# TPDH-Walrus_4pinPTH.net
KiCad netlist of a schematic drawn in EAGLE
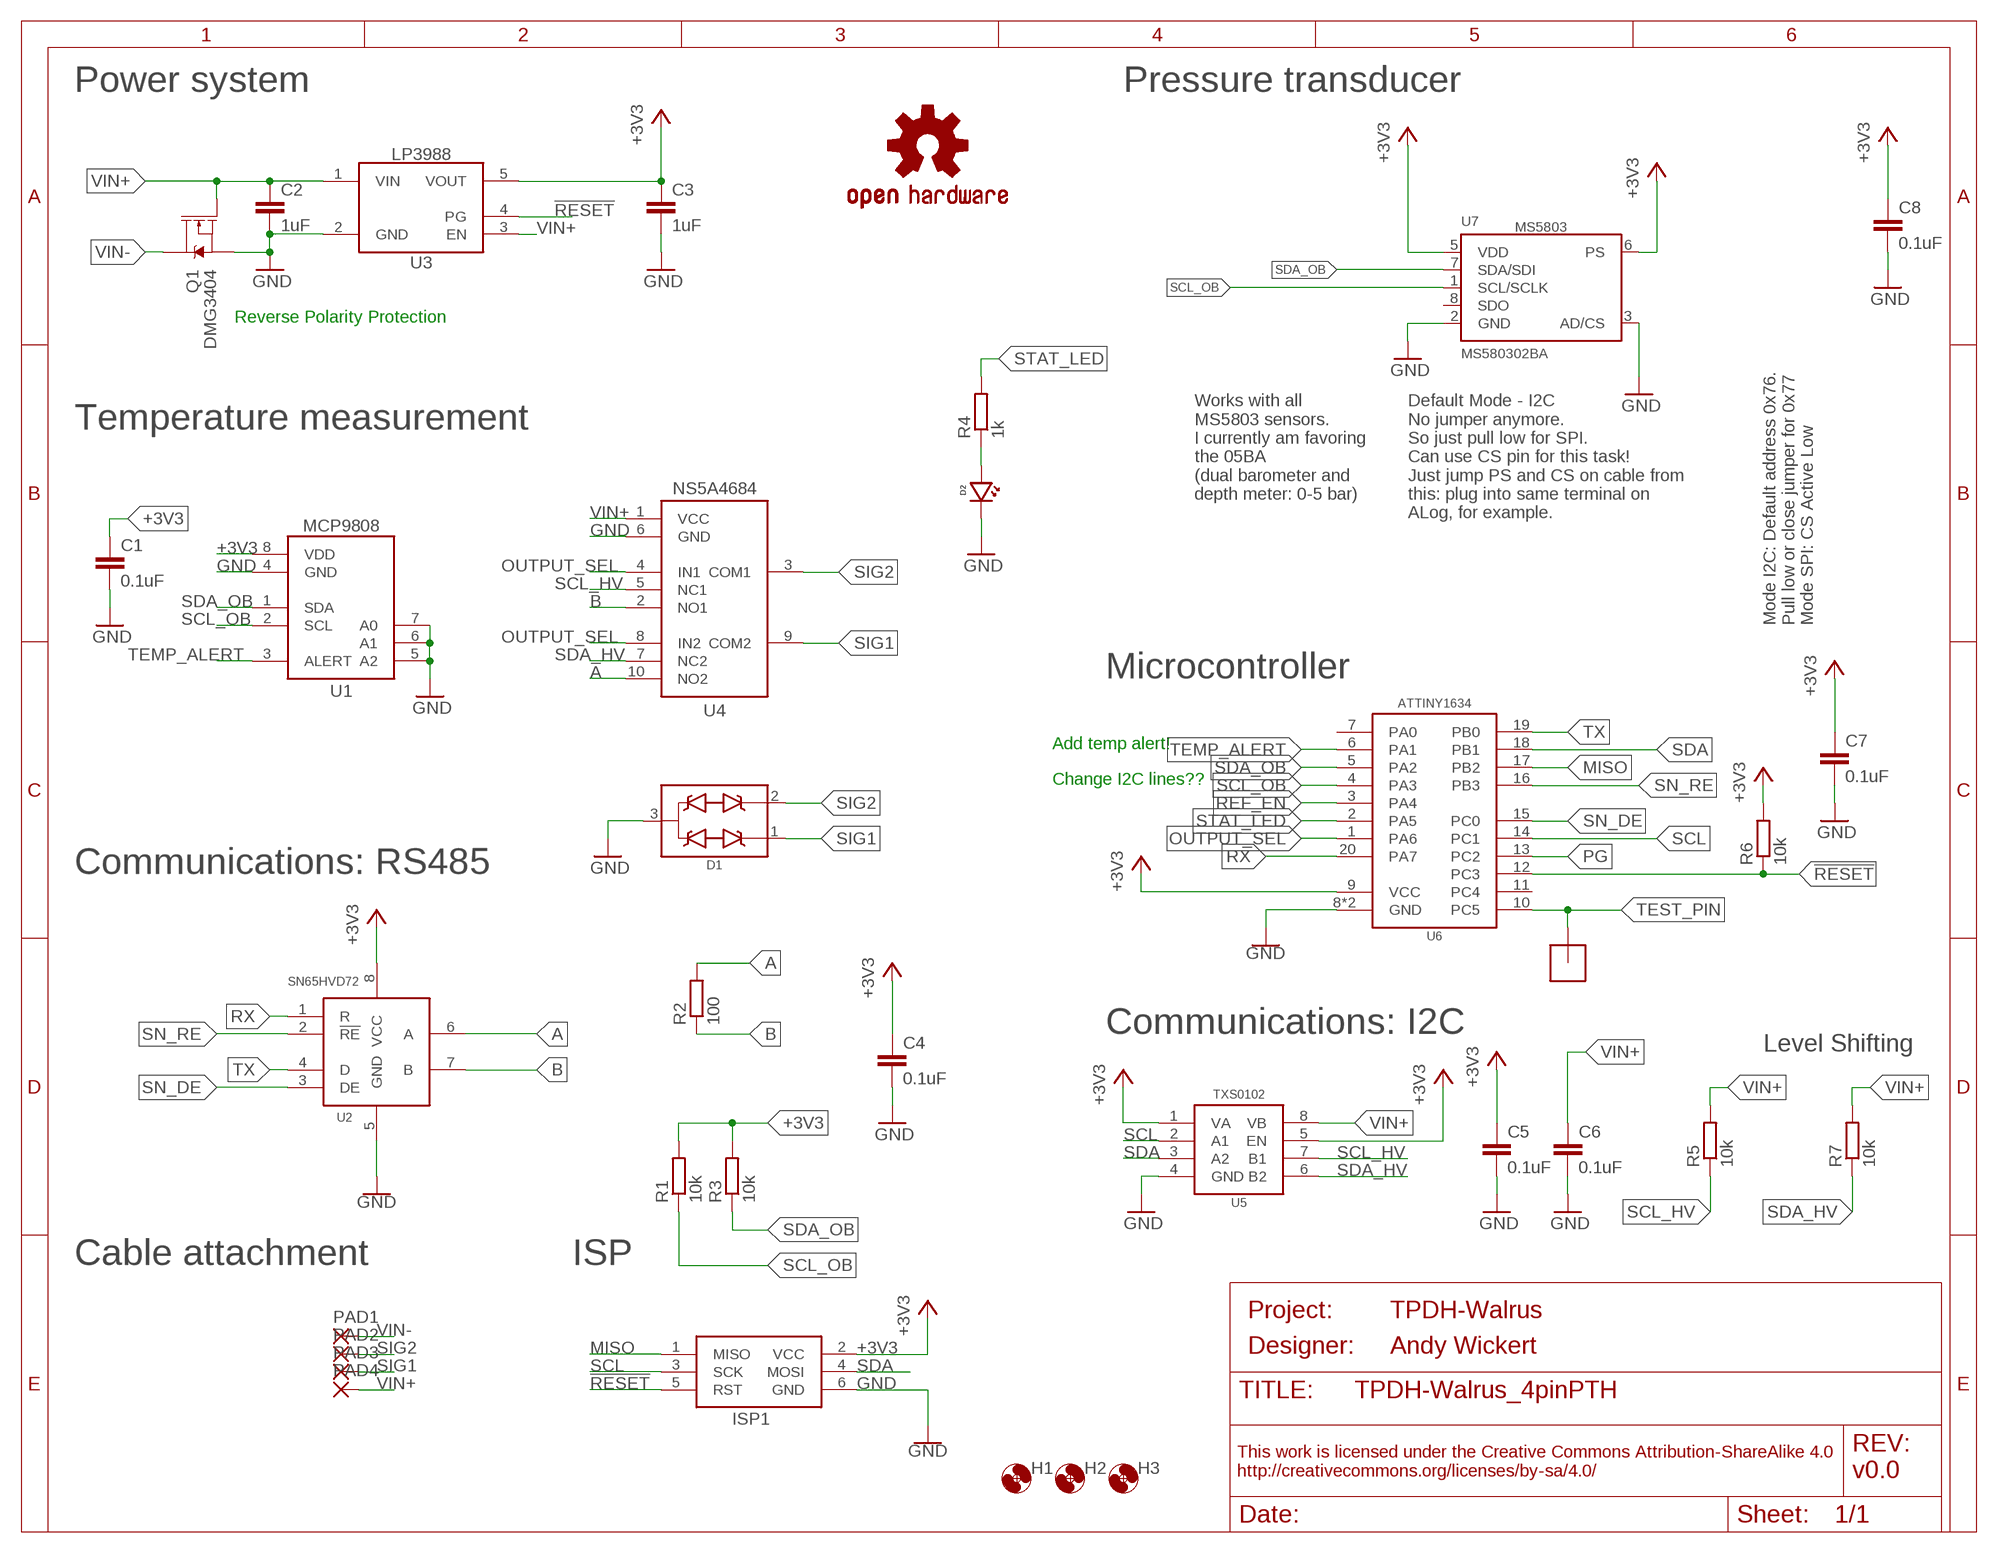
[diagram p0: schematic, sheet 1]

(export (version "E")
  (design (tool "Eeschema 10.0.6"))
  (components
    (comp (ref "C1")
      (value "0.1uF")
      (footprint "eagle-import:C0402")
      (fields (field (name "MF") "Murata") (field (name "MPN") "GCM155R71C104KA55D"))
      (libsource (lib "eagle-import") (part "C-EUC04020.1UF"))
    )
    (comp (ref "C2")
      (value "1uF")
      (footprint "eagle-import:C0603")
      (fields (field (name "MF") "Samsung") (field (name "MPN") "1276-6524-1-ND"))
      (libsource (lib "eagle-import") (part "C-EUC06031UF"))
    )
    (comp (ref "C3")
      (value "1uF")
      (footprint "eagle-import:C0603")
      (fields (field (name "MF") "Samsung") (field (name "MPN") "1276-6524-1-ND"))
      (libsource (lib "eagle-import") (part "C-EUC06031UF"))
    )
    (comp (ref "C4")
      (value "0.1uF")
      (footprint "eagle-import:C0402")
      (fields (field (name "MF") "Murata") (field (name "MPN") "GCM155R71C104KA55D"))
      (libsource (lib "eagle-import") (part "C-EUC04020.1UF"))
    )
    (comp (ref "C5")
      (value "0.1uF")
      (footprint "eagle-import:C0402")
      (fields (field (name "MF") "Murata") (field (name "MPN") "GCM155R71C104KA55D"))
      (libsource (lib "eagle-import") (part "C-EUC04020.1UF"))
    )
    (comp (ref "C6")
      (value "0.1uF")
      (footprint "eagle-import:C0402")
      (fields (field (name "MF") "Murata") (field (name "MPN") "GCM155R71C104KA55D"))
      (libsource (lib "eagle-import") (part "C-EUC04020.1UF"))
    )
    (comp (ref "C7")
      (value "0.1uF")
      (footprint "eagle-import:C0402")
      (fields (field (name "MF") "Murata") (field (name "MPN") "GCM155R71C104KA55D"))
      (libsource (lib "eagle-import") (part "C-EUC04020.1UF"))
    )
    (comp (ref "C8")
      (value "0.1uF")
      (footprint "eagle-import:C0402")
      (fields (field (name "MF") "Murata") (field (name "MPN") "GCM155R71C104KA55D"))
      (libsource (lib "eagle-import") (part "C-EUC04020.1UF"))
    )
    (comp (ref "D1")
      (value "TVSSM712")
      (footprint "eagle-import:SOT23-3")
      (fields (field (name "MF") "Bourns") (field (name "MPN") "CDSOT23-SM712"))
      (libsource (lib "eagle-import") (part "TVSSM712"))
    )
    (comp (ref "D2")
      (value "LEDBLUE0603")
      (footprint "eagle-import:LED_0603")
      (fields (field (name "MF") "Wurth") (field (name "MPN") "150060BS75000"))
      (libsource (lib "eagle-import") (part "LED0603BLUE"))
    )
    (comp (ref "H1")
      (value "MOUNTING_HOLE2_NP")
      (footprint "eagle-import:2_56")
      (libsource (lib "eagle-import") (part "MOUNTING_HOLE2_NP"))
    )
    (comp (ref "H2")
      (value "MOUNTING_HOLE2_NP")
      (footprint "eagle-import:2_56")
      (libsource (lib "eagle-import") (part "MOUNTING_HOLE2_NP"))
    )
    (comp (ref "H3")
      (value "MOUNTING_HOLE2_NP")
      (footprint "eagle-import:2_56")
      (libsource (lib "eagle-import") (part "MOUNTING_HOLE2_NP"))
    )
    (comp (ref "ISP1")
      (value "AVRISP-6")
      (footprint "eagle-import:AVRISP")
      (libsource (lib "eagle-import") (part "AVRISP-6"))
    )
    (comp (ref "LOGO1")
      (value "OSHW-LOGOM")
      (footprint "eagle-import:OSHW-LOGO-M")
      (libsource (lib "eagle-import") (part "OSHW-LOGOM"))
    )
    (comp (ref "PAD1")
      (value "PAD1.1MM")
      (footprint "eagle-import:2,54_1,1")
      (libsource (lib "eagle-import") (part "PAD1.1MM"))
    )
    (comp (ref "PAD2")
      (value "PAD1.1MM")
      (footprint "eagle-import:2,54_1,1")
      (libsource (lib "eagle-import") (part "PAD1.1MM"))
    )
    (comp (ref "PAD3")
      (value "PAD1.1MM")
      (footprint "eagle-import:2,54_1,1")
      (libsource (lib "eagle-import") (part "PAD1.1MM"))
    )
    (comp (ref "PAD4")
      (value "PAD1.1MM")
      (footprint "eagle-import:2,54_1,1")
      (libsource (lib "eagle-import") (part "PAD1.1MM"))
    )
    (comp (ref "Q1")
      (value "DMG3404")
      (footprint "eagle-import:SOT23-3")
      (fields (field (name "MF") "Diodes Incorporated") (field (name "MPN") "DMG3404L-7"))
      (libsource (lib "eagle-import") (part "MOSFET-NCH-DMG3404L"))
    )
    (comp (ref "R1")
      (value "10k")
      (footprint "eagle-import:R0402")
      (fields (field (name "MF") "Yageo") (field (name "MPN") "RC0402FR-0710KL"))
      (libsource (lib "eagle-import") (part "R-EU_R040210K"))
    )
    (comp (ref "R2")
      (value "100")
      (footprint "eagle-import:R0402")
      (fields (field (name "MF") "Yageo") (field (name "MPN") "RC0402FR-07100RL"))
      (libsource (lib "eagle-import") (part "R-EU_R0402100"))
    )
    (comp (ref "R3")
      (value "10k")
      (footprint "eagle-import:R0402")
      (fields (field (name "MF") "Yageo") (field (name "MPN") "RC0402FR-0710KL"))
      (libsource (lib "eagle-import") (part "R-EU_R040210K"))
    )
    (comp (ref "R4")
      (value "1k")
      (footprint "eagle-import:R0603")
      (fields (field (name "MF") "Yageo") (field (name "MPN") "AC0603FR-071KL"))
      (libsource (lib "eagle-import") (part "R-EU_R06031K"))
    )
    (comp (ref "R5")
      (value "10k")
      (footprint "eagle-import:R0402")
      (fields (field (name "MF") "Yageo") (field (name "MPN") "RC0402FR-0710KL"))
      (libsource (lib "eagle-import") (part "R-EU_R040210K"))
    )
    (comp (ref "R6")
      (value "10k")
      (footprint "eagle-import:R0402")
      (fields (field (name "MF") "Yageo") (field (name "MPN") "RC0402FR-0710KL"))
      (libsource (lib "eagle-import") (part "R-EU_R040210K"))
    )
    (comp (ref "R7")
      (value "10k")
      (footprint "eagle-import:R0402")
      (fields (field (name "MF") "Yageo") (field (name "MPN") "RC0402FR-0710KL"))
      (libsource (lib "eagle-import") (part "R-EU_R040210K"))
    )
    (comp (ref "TP1")
      (value "POGO_PAD")
      (footprint "eagle-import:POGO_PAD")
      (libsource (lib "eagle-import") (part "POGO_PAD"))
    )
    (comp (ref "U1")
      (value "MCP9808MSOP")
      (footprint "eagle-import:MSOP_8")
      (fields (field (name "MF") "Microchip") (field (name "MPN") "MCP9808T-E/MS"))
      (libsource (lib "eagle-import") (part "MCP9808MSOP"))
    )
    (comp (ref "U2")
      (value "SN65HVD72DSOIC")
      (footprint "eagle-import:SO08")
      (fields (field (name "DISP") "SN65HVD72") (field (name "MF") "TI") (field (name "MPN") "SN65HVD72DR"))
      (libsource (lib "eagle-import") (part "SN65HVD72SOICD"))
    )
    (comp (ref "U3")
      (value "LP39883.3VDBV")
      (footprint "eagle-import:DBV0005A")
      (fields (field (name "MF") "TI") (field (name "MPN") "LP3988IMF-3.3/NOPB"))
      (libsource (lib "eagle-import") (part "LP3988DBV3.3V"))
    )
    (comp (ref "U4")
      (value "NS5A4684S")
      (footprint "eagle-import:WQFN10")
      (fields
        (field (name "DISP") "NS5A4684")
        (field (name "MF") "ON Semiconductor")
        (field (name "MPN") "NS5A4684SMNTAG")
      )
      (libsource (lib "eagle-import") (part "NS5A4684S"))
    )
    (comp (ref "U5")
      (value "TXS0102DQM")
      (footprint "eagle-import:DQM_R-PX2SON-N8")
      (fields (field (name "MF") "TI") (field (name "MPN") "TXS0102DQMR"))
      (libsource (lib "eagle-import") (part "TXS0102DQM"))
    )
    (comp (ref "U6")
      (value "ATTINY1634QFN")
      (footprint "eagle-import:QFN20")
      (fields (field (name "MF") "Atmel") (field (name "MPN") "ATTINY1634-MUR"))
      (libsource (lib "eagle-import") (part "ATTINY1634QFN"))
    )
    (comp (ref "U7")
      (value "MS580302BA")
      (footprint "eagle-import:MS5803")
      (fields
        (field (name "MF") "TE Connectivity")
        (field (name "MF_1") "TE")
        (field (name "MPN") "MS580305BA01-00")
      )
      (libsource (lib "eagle-import") (part "MS580302BA"))
    )
  )
  (nets
    (net (code "1") (name "+3V3") (class "Default")
      (node (ref "C1") (pin "1") (pinfunction "1_1") (pintype "passive"))
      (node (ref "C3") (pin "1") (pinfunction "1_1") (pintype "passive"))
      (node (ref "C4") (pin "1") (pinfunction "1_1") (pintype "passive"))
      (node (ref "C5") (pin "1") (pinfunction "1_1") (pintype "passive"))
      (node (ref "C7") (pin "1") (pinfunction "1_1") (pintype "passive"))
      (node (ref "C8") (pin "1") (pinfunction "1_1") (pintype "passive"))
      (node (ref "ISP1") (pin "2") (pinfunction "VCC_2") (pintype "power_in"))
      (node (ref "R1") (pin "2") (pinfunction "2_2") (pintype "passive"))
      (node (ref "R3") (pin "2") (pinfunction "2_2") (pintype "passive"))
      (node (ref "R6") (pin "2") (pinfunction "2_2") (pintype "passive"))
      (node (ref "U1") (pin "8") (pinfunction "VDD_8") (pintype "power_in"))
      (node (ref "U2") (pin "8") (pinfunction "VCC_8") (pintype "power_in"))
      (node (ref "U3") (pin "5") (pinfunction "VOUT_5") (pintype "power_in"))
      (node (ref "U5") (pin "1") (pinfunction "VA_1") (pintype "power_in"))
      (node (ref "U5") (pin "5") (pinfunction "EN_5") (pintype "input"))
      (node (ref "U6") (pin "9") (pinfunction "VCC_9") (pintype "power_in"))
      (node (ref "U7") (pin "5") (pinfunction "VDD_5") (pintype "power_in"))
      (node (ref "U7") (pin "6") (pinfunction "PS_6") (pintype "input"))
    )
    (net (code "2") (name "/~{RESET}") (class "Default")
      (node (ref "ISP1") (pin "5") (pinfunction "RST_5") (pintype "output"))
      (node (ref "R6") (pin "1") (pinfunction "1_1") (pintype "passive"))
      (node (ref "U3") (pin "4") (pinfunction "PG_4") (pintype "output"))
      (node (ref "U6") (pin "12") (pinfunction "PC3_12") (pintype "bidirectional"))
    )
    (net (code "3") (name "A") (class "Default")
      (node (ref "R2") (pin "2") (pinfunction "2_2") (pintype "passive"))
      (node (ref "U2") (pin "6") (pinfunction "A_6") (pintype "bidirectional"))
      (node (ref "U4") (pin "10") (pinfunction "NO2_10") (pintype "bidirectional"))
    )
    (net (code "4") (name "B") (class "Default")
      (node (ref "R2") (pin "1") (pinfunction "1_1") (pintype "passive"))
      (node (ref "U2") (pin "7") (pinfunction "B_7") (pintype "bidirectional"))
      (node (ref "U4") (pin "2") (pinfunction "NO1_2") (pintype "bidirectional"))
    )
    (net (code "5") (name "GND") (class "Default")
      (node (ref "C1") (pin "2") (pinfunction "2_2") (pintype "passive"))
      (node (ref "C2") (pin "2") (pinfunction "2_2") (pintype "passive"))
      (node (ref "C3") (pin "2") (pinfunction "2_2") (pintype "passive"))
      (node (ref "C4") (pin "2") (pinfunction "2_2") (pintype "passive"))
      (node (ref "C5") (pin "2") (pinfunction "2_2") (pintype "passive"))
      (node (ref "C6") (pin "2") (pinfunction "2_2") (pintype "passive"))
      (node (ref "C7") (pin "2") (pinfunction "2_2") (pintype "passive"))
      (node (ref "C8") (pin "2") (pinfunction "2_2") (pintype "passive"))
      (node (ref "D1") (pin "3") (pinfunction "COM_3") (pintype "input"))
      (node (ref "D2") (pin "CATHODE") (pinfunction "CATHODE_CATHODE") (pintype "power_in"))
      (node (ref "ISP1") (pin "6") (pinfunction "GND_6") (pintype "power_in"))
      (node (ref "Q1") (pin "2") (pinfunction "S_2") (pintype "bidirectional"))
      (node (ref "U1") (pin "4") (pinfunction "GND_4") (pintype "power_in"))
      (node (ref "U1") (pin "5") (pinfunction "A2_5") (pintype "input"))
      (node (ref "U1") (pin "6") (pinfunction "A1_6") (pintype "input"))
      (node (ref "U1") (pin "7") (pinfunction "A0_7") (pintype "input"))
      (node (ref "U2") (pin "5") (pinfunction "GND_5") (pintype "power_in"))
      (node (ref "U3") (pin "2") (pinfunction "GND_2") (pintype "power_in"))
      (node (ref "U4") (pin "6") (pinfunction "GND_6") (pintype "power_in"))
      (node (ref "U5") (pin "4") (pinfunction "GND_4") (pintype "power_in"))
      (node (ref "U6") (pin "8") (pinfunction "GND_8") (pintype "power_in"))
      (node (ref "U6") (pin "EP") (pinfunction "GND_EP") (pintype "power_in"))
      (node (ref "U7") (pin "2") (pinfunction "GND_2") (pintype "power_in"))
      (node (ref "U7") (pin "3") (pinfunction "AD/CS_3") (pintype "input"))
    )
    (net (code "6") (name "MISO") (class "Default")
      (node (ref "ISP1") (pin "1") (pinfunction "MISO_1") (pintype "input"))
      (node (ref "U6") (pin "17") (pinfunction "PB2_17") (pintype "bidirectional"))
    )
    (net (code "7") (name "Net-(D2-PadANODE)") (class "Default")
      (node (ref "D2") (pin "ANODE") (pinfunction "ANODE_ANODE") (pintype "power_in"))
      (node (ref "R4") (pin "1") (pinfunction "1_1") (pintype "passive"))
    )
    (net (code "8") (name "OUTPUT_SEL") (class "Default")
      (node (ref "U4") (pin "4") (pinfunction "IN1_4") (pintype "input"))
      (node (ref "U4") (pin "8") (pinfunction "IN2_8") (pintype "input"))
      (node (ref "U6") (pin "1") (pinfunction "PA6_1") (pintype "bidirectional"))
    )
    (net (code "9") (name "PG") (class "Default")
      (node (ref "U6") (pin "13") (pinfunction "PC2_13") (pintype "bidirectional"))
    )
    (net (code "10") (name "REF_EN") (class "Default")
      (node (ref "U6") (pin "3") (pinfunction "PA4_3") (pintype "bidirectional"))
    )
    (net (code "11") (name "RX") (class "Default")
      (node (ref "U2") (pin "1") (pinfunction "R_1") (pintype "output"))
      (node (ref "U6") (pin "20") (pinfunction "PA7_20") (pintype "bidirectional"))
    )
    (net (code "12") (name "SCL") (class "Default")
      (node (ref "ISP1") (pin "3") (pinfunction "SCK_3") (pintype "output"))
      (node (ref "U5") (pin "2") (pinfunction "A1_2") (pintype "bidirectional"))
      (node (ref "U6") (pin "14") (pinfunction "PC1_14") (pintype "bidirectional"))
    )
    (net (code "13") (name "SCL_HV") (class "Default")
      (node (ref "R5") (pin "1") (pinfunction "1_1") (pintype "passive"))
      (node (ref "U4") (pin "5") (pinfunction "NC1_5") (pintype "bidirectional"))
      (node (ref "U5") (pin "7") (pinfunction "B1_7") (pintype "bidirectional"))
    )
    (net (code "14") (name "SCL_OB") (class "Default")
      (node (ref "R1") (pin "1") (pinfunction "1_1") (pintype "passive"))
      (node (ref "U1") (pin "2") (pinfunction "SCL_2") (pintype "input"))
      (node (ref "U6") (pin "4") (pinfunction "PA3_4") (pintype "bidirectional"))
      (node (ref "U7") (pin "1") (pinfunction "SCL/SCLK_1") (pintype "input"))
    )
    (net (code "15") (name "SDA") (class "Default")
      (node (ref "ISP1") (pin "4") (pinfunction "MOSI_4") (pintype "output"))
      (node (ref "U5") (pin "3") (pinfunction "A2_3") (pintype "bidirectional"))
      (node (ref "U6") (pin "18") (pinfunction "PB1_18") (pintype "bidirectional"))
    )
    (net (code "16") (name "SDA_HV") (class "Default")
      (node (ref "R7") (pin "1") (pinfunction "1_1") (pintype "passive"))
      (node (ref "U4") (pin "7") (pinfunction "NC2_7") (pintype "bidirectional"))
      (node (ref "U5") (pin "6") (pinfunction "B2_6") (pintype "bidirectional"))
    )
    (net (code "17") (name "SDA_OB") (class "Default")
      (node (ref "R3") (pin "1") (pinfunction "1_1") (pintype "passive"))
      (node (ref "U1") (pin "1") (pinfunction "SDA_1") (pintype "bidirectional"))
      (node (ref "U6") (pin "5") (pinfunction "PA2_5") (pintype "bidirectional"))
      (node (ref "U7") (pin "7") (pinfunction "SDA/SDI_7") (pintype "bidirectional"))
    )
    (net (code "18") (name "SIG1") (class "Default")
      (node (ref "D1") (pin "1") (pinfunction "D1_1") (pintype "input"))
      (node (ref "PAD3") (pin "1") (pinfunction "P_1") (pintype "passive"))
      (node (ref "U4") (pin "9") (pinfunction "COM2_9") (pintype "bidirectional"))
    )
    (net (code "19") (name "SIG2") (class "Default")
      (node (ref "D1") (pin "2") (pinfunction "D2_2") (pintype "input"))
      (node (ref "PAD2") (pin "1") (pinfunction "P_1") (pintype "passive"))
      (node (ref "U4") (pin "3") (pinfunction "COM1_3") (pintype "bidirectional"))
    )
    (net (code "20") (name "SN_DE") (class "Default")
      (node (ref "U2") (pin "3") (pinfunction "DE_3") (pintype "input"))
      (node (ref "U6") (pin "15") (pinfunction "PC0_15") (pintype "bidirectional"))
    )
    (net (code "21") (name "SN_RE") (class "Default")
      (node (ref "U2") (pin "2") (pinfunction "~{RE}_2") (pintype "input"))
      (node (ref "U6") (pin "16") (pinfunction "PB3_16") (pintype "bidirectional"))
    )
    (net (code "22") (name "STAT_LED") (class "Default")
      (node (ref "R4") (pin "2") (pinfunction "2_2") (pintype "passive"))
      (node (ref "U6") (pin "2") (pinfunction "PA5_2") (pintype "bidirectional"))
    )
    (net (code "23") (name "TEMP_ALERT") (class "Default")
      (node (ref "U1") (pin "3") (pinfunction "ALERT_3") (pintype "output"))
      (node (ref "U6") (pin "6") (pinfunction "PA1_6") (pintype "bidirectional"))
    )
    (net (code "24") (name "TEST_PIN") (class "Default")
      (node (ref "TP1") (pin "P$1") (pinfunction "P$1_P$1") (pintype "bidirectional"))
      (node (ref "U6") (pin "10") (pinfunction "PC5_10") (pintype "bidirectional"))
    )
    (net (code "25") (name "TX") (class "Default")
      (node (ref "U2") (pin "4") (pinfunction "D_4") (pintype "input"))
      (node (ref "U6") (pin "19") (pinfunction "PB0_19") (pintype "bidirectional"))
    )
    (net (code "26") (name "VIN+") (class "Default")
      (node (ref "C2") (pin "1") (pinfunction "1_1") (pintype "passive"))
      (node (ref "C6") (pin "1") (pinfunction "1_1") (pintype "passive"))
      (node (ref "PAD4") (pin "1") (pinfunction "P_1") (pintype "passive"))
      (node (ref "Q1") (pin "1") (pinfunction "G_1") (pintype "bidirectional"))
      (node (ref "R5") (pin "2") (pinfunction "2_2") (pintype "passive"))
      (node (ref "R7") (pin "2") (pinfunction "2_2") (pintype "passive"))
      (node (ref "U3") (pin "1") (pinfunction "VIN_1") (pintype "power_in"))
      (node (ref "U3") (pin "3") (pinfunction "EN_3") (pintype "input"))
      (node (ref "U4") (pin "1") (pinfunction "VCC_1") (pintype "power_in"))
      (node (ref "U5") (pin "8") (pinfunction "VB_8") (pintype "power_in"))
    )
    (net (code "27") (name "VIN-") (class "Default")
      (node (ref "PAD1") (pin "1") (pinfunction "P_1") (pintype "passive"))
      (node (ref "Q1") (pin "3") (pinfunction "D_3") (pintype "bidirectional"))
    )
    (net (code "28") (name "unconnected-(U6-PA0-Pad7)") (class "Default")
      (node (ref "U6") (pin "7") (pinfunction "PA0_7") (pintype "bidirectional"))
    )
    (net (code "29") (name "unconnected-(U6-PC4-Pad11)") (class "Default")
      (node (ref "U6") (pin "11") (pinfunction "PC4_11") (pintype "bidirectional"))
    )
    (net (code "30") (name "unconnected-(U7-SDO-Pad8)") (class "Default")
      (node (ref "U7") (pin "8") (pinfunction "SDO_8") (pintype "output"))
    )
  )
)
